# 1-Schematic_WaterTank_reciever_v1.net
KiCad netlist of a schematic drawn in EasyEDA
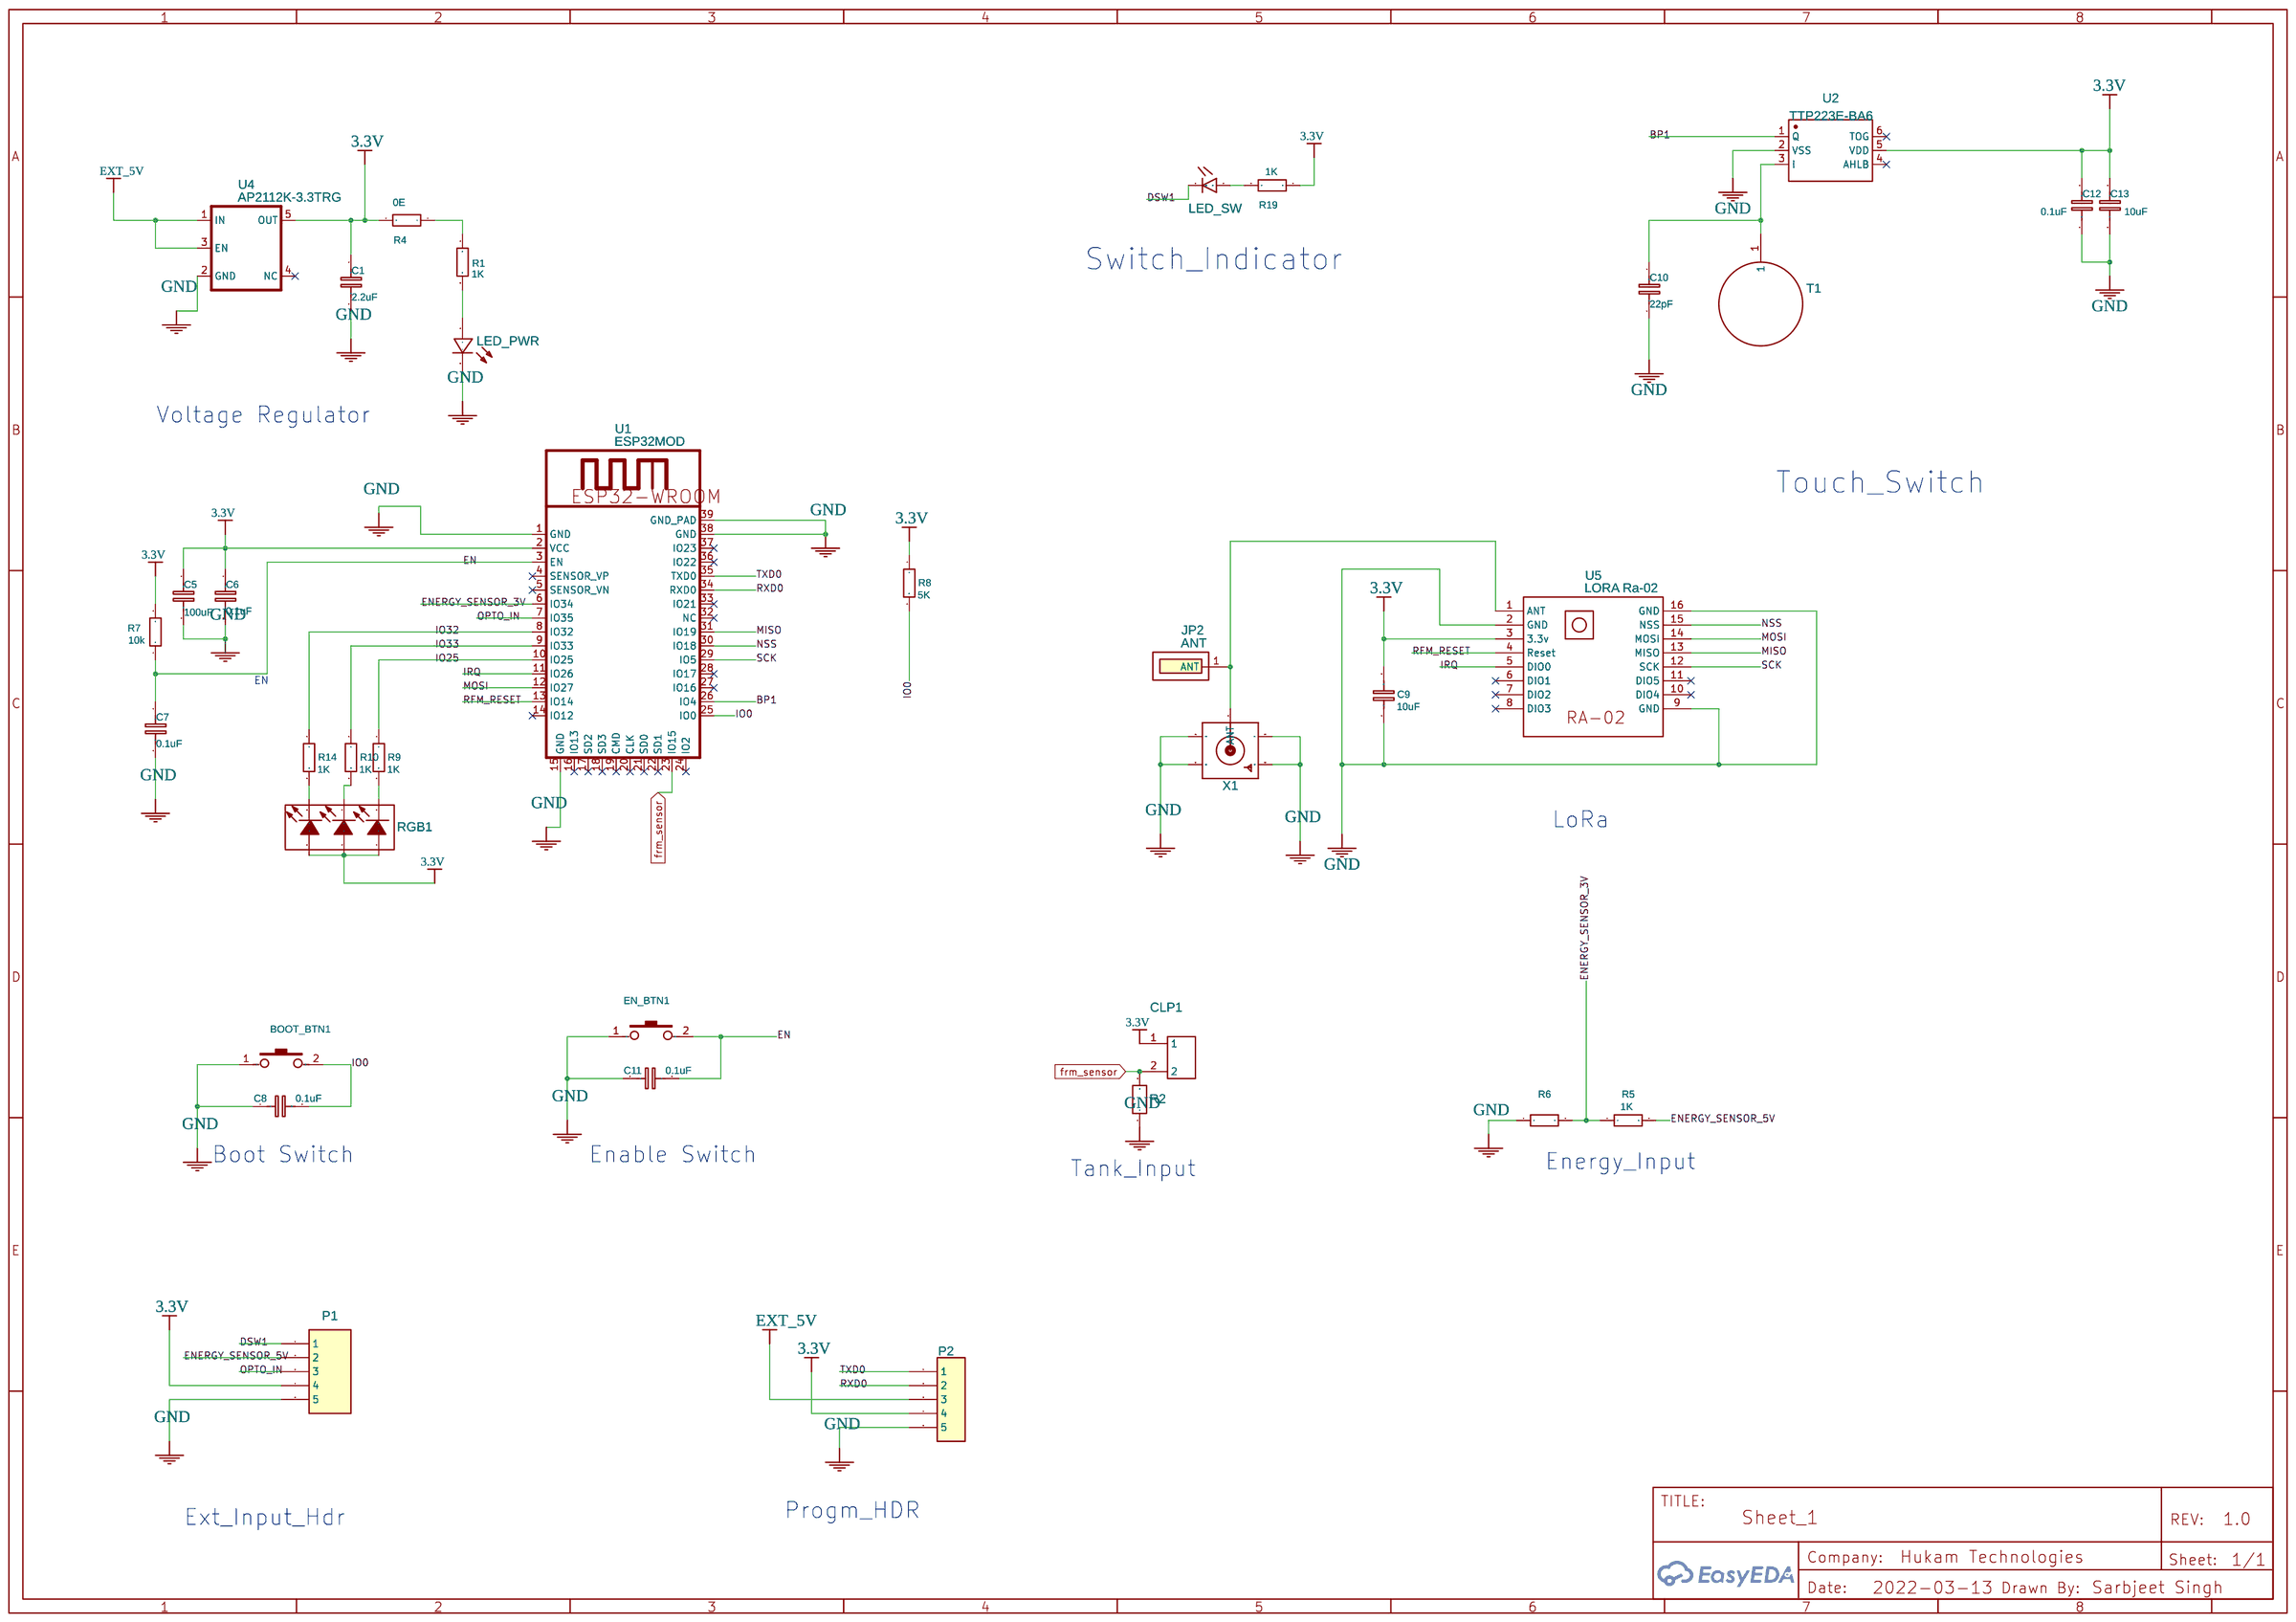
[diagram p0: schematic sheet]

(export (version "E")
  (design (tool "Eeschema 10.0.6"))
  (components
    (comp (ref "BOOT_BTN1")
      (value "SW1")
      (fields
        (field (name "BOM_Manufacturer Part") "Switch3x4x2")
        (field (name "BOM_Supplier Part") "C26638")
      )
      (libsource (lib "") (part "Unknown_195_-50"))
    )
    (comp (ref "C1")
      (value "2.2uF")
      (fields (field (name "BOM_Manufacturer Part") "?"))
      (libsource (lib "") (part "Capacitor_3"))
    )
    (comp (ref "C5")
      (value "100uF")
      (fields (field (name "BOM_Manufacturer Part") "?"))
      (libsource (lib "") (part "Capacitor_4"))
    )
    (comp (ref "C6")
      (value "0.1uF")
      (fields (field (name "BOM_Manufacturer Part") "?"))
      (libsource (lib "") (part "Capacitor_5"))
    )
    (comp (ref "C7")
      (value "0.1uF")
      (fields (field (name "BOM_Manufacturer Part") "?"))
      (libsource (lib "") (part "Capacitor_4"))
    )
    (comp (ref "C8")
      (value "0.1uF")
      (fields (field (name "BOM_Manufacturer Part") "?"))
      (libsource (lib "") (part "Capacitor_2"))
    )
    (comp (ref "C9")
      (value "10uF")
      (fields (field (name "BOM_Manufacturer Part") "?"))
      (libsource (lib "") (part "Capacitor_1"))
    )
    (comp (ref "C10")
      (value "22pF")
      (fields (field (name "BOM_Manufacturer Part") "?"))
      (libsource (lib "") (part "Capacitor"))
    )
    (comp (ref "C11")
      (value "0.1uF")
      (fields (field (name "BOM_Manufacturer Part") "?"))
      (libsource (lib "") (part "Capacitor_2"))
    )
    (comp (ref "C12")
      (value "0.1uF")
      (fields (field (name "BOM_Manufacturer Part") "?"))
      (libsource (lib "") (part "Capacitor"))
    )
    (comp (ref "C13")
      (value "10uF")
      (fields (field (name "BOM_Manufacturer Part") "?"))
      (libsource (lib "") (part "Capacitor"))
    )
    (comp (ref "CLP1") (value "JST_Conn_Water_Level") (libsource (lib "") (part "PCB JST XH2.54mm")))
    (comp (ref "EN_BTN1")
      (value "SW2")
      (fields
        (field (name "BOM_Manufacturer Part") "Switch3x4x2")
        (field (name "BOM_Supplier Part") "C26638")
      )
      (libsource (lib "") (part "Unknown_460_-70"))
    )
    (comp (ref "JP2")
      (value "ANT")
      (fields (field (name "BOM_Manufacturer Part") "?"))
      (libsource (lib "") (part "Unknown_875_-335"))
    )
    (comp (ref "LED_PWR")
      (value "LED-Blue(0603)")
      (fields
        (field (name "BOM_Manufacturer Part") "19-217/BHC-ZL1M2RY/3T")
        (field (name "BOM_Supplier Part") "undefined")
      )
      (libsource (lib "") (part "Unknown_325_-565"))
    )
    (comp (ref "LED_SW")
      (value "LED_Indicator")
      (fields (field (name "BOM_Manufacturer Part") "?"))
      (libsource (lib "") (part "Unknown_855_-680"))
    )
    (comp (ref "P1") (value "Ext_HDR") (libsource (lib "") (part "Header 5")))
    (comp (ref "P2")
      (value "HDR1X5")
      (fields (field (name "BOM_Manufacturer Part") "?"))
      (libsource (lib "") (part "Unknown_685_180"))
    )
    (comp (ref "R1")
      (value "1K")
      (fields (field (name "BOM_Manufacturer Part") "?"))
      (libsource (lib "") (part "Resistor"))
    )
    (comp (ref "R2") (value "1k") (libsource (lib "") (part "R_0603_EU")))
    (comp (ref "R4")
      (value "0E")
      (fields (field (name "BOM_Manufacturer Part") "?"))
      (libsource (lib "") (part "Resistor_2"))
    )
    (comp (ref "R5")
      (value "1K")
      (fields (field (name "BOM_Manufacturer Part") "?"))
      (libsource (lib "") (part "Resistor_1"))
    )
    (comp (ref "R6")
      (value "1K")
      (fields (field (name "BOM_Manufacturer Part") "?"))
      (libsource (lib "") (part "Resistor_1"))
    )
    (comp (ref "R7")
      (value "10k")
      (fields (field (name "BOM_Manufacturer Part") "?"))
      (libsource (lib "") (part "Resistor_3"))
    )
    (comp (ref "R8")
      (value "5K")
      (fields (field (name "BOM_Manufacturer Part") "?"))
      (libsource (lib "") (part "Resistor"))
    )
    (comp (ref "R9")
      (value "1K")
      (fields (field (name "BOM_Manufacturer Part") "?"))
      (libsource (lib "") (part "Resistor"))
    )
    (comp (ref "R10")
      (value "1K")
      (fields (field (name "BOM_Manufacturer Part") "?"))
      (libsource (lib "") (part "Resistor"))
    )
    (comp (ref "R14")
      (value "1K")
      (fields (field (name "BOM_Manufacturer Part") "?"))
      (libsource (lib "") (part "Resistor"))
    )
    (comp (ref "R19")
      (value "1K")
      (fields (field (name "BOM_Manufacturer Part") "?"))
      (libsource (lib "") (part "Resistor_2"))
    )
    (comp (ref "RGB1")
      (value "5050QRC")
      (fields (field (name "BOM_Supplier Part") "C42899"))
      (libsource (lib "") (part "Unknown_235_-220"))
    )
    (comp (ref "T1")
      (value "CapTouch Pad")
      (fields (field (name "BOM_Manufacturer Part") "?"))
      (libsource (lib "") (part "Unknown_1255_-625"))
    )
    (comp (ref "U1")
      (value "ESP32MOD")
      (fields (field (name "BOM_Manufacturer Part") "?"))
      (libsource (lib "") (part "Unknown_445_-380"))
    )
    (comp (ref "U2")
      (value "TTP223E-BA6")
      (fields (field (name "BOM_Supplier Part") "C129457"))
      (libsource (lib "") (part "Unknown_1305_-725"))
    )
    (comp (ref "U4")
      (value "AP2112K-3.3TRG")
      (fields (field (name "BOM_Manufacturer Part") "?"))
      (libsource (lib "") (part "Unknown_165_-625"))
    )
    (comp (ref "U5")
      (value "LORA Ra-02")
      (fields (field (name "BOM_Supplier Part") "RA-02"))
      (libsource (lib "") (part "Unknown_1145_-305"))
    )
    (comp (ref "X1")
      (value "SMACONNECTOR_EDGE_UFL")
      (fields (field (name "BOM_Manufacturer Part") "?"))
      (libsource (lib "") (part "Unknown_875_-275"))
    )
  )
  (nets
    (net (code "1") (name "/BP1") (class "Default")
      (node (ref "U1") (pin "26") (pinfunction "IO4_26") (pintype "unspecified"))
      (node (ref "U2") (pin "1") (pinfunction "Q_1") (pintype "unspecified"))
    )
    (net (code "2") (name "/DSW1") (class "Default")
      (node (ref "LED_SW") (pin "2") (pinfunction "CATHODE_2") (pintype "unspecified"))
      (node (ref "P1") (pin "1") (pinfunction "1_1") (pintype "unspecified"))
    )
    (net (code "3") (name "/EN") (class "Default")
      (node (ref "C11") (pin "2") (pinfunction "2_2") (pintype "unspecified"))
      (node (ref "C7") (pin "1") (pinfunction "1_1") (pintype "unspecified"))
      (node (ref "EN_BTN1") (pin "2") (pinfunction "2_2") (pintype "input"))
      (node (ref "R7") (pin "1") (pinfunction "1_1") (pintype "unspecified"))
      (node (ref "U1") (pin "3") (pinfunction "EN_3") (pintype "unspecified"))
    )
    (net (code "4") (name "/ENERGY_SENSOR_3V") (class "Default")
      (node (ref "R5") (pin "1") (pinfunction "1_1") (pintype "unspecified"))
      (node (ref "R6") (pin "2") (pinfunction "2_2") (pintype "unspecified"))
      (node (ref "U1") (pin "6") (pinfunction "IO34_6") (pintype "unspecified"))
    )
    (net (code "5") (name "/ENERGY_SENSOR_5V") (class "Default")
      (node (ref "P1") (pin "2") (pinfunction "2_2") (pintype "unspecified"))
      (node (ref "R5") (pin "2") (pinfunction "2_2") (pintype "unspecified"))
    )
    (net (code "6") (name "/IO0") (class "Default")
      (node (ref "BOOT_BTN1") (pin "2") (pinfunction "2_2") (pintype "input"))
      (node (ref "C8") (pin "2") (pinfunction "2_2") (pintype "unspecified"))
      (node (ref "R8") (pin "2") (pinfunction "2_2") (pintype "unspecified"))
      (node (ref "U1") (pin "25") (pinfunction "IO0_25") (pintype "unspecified"))
    )
    (net (code "7") (name "/IO25") (class "Default")
      (node (ref "R9") (pin "1") (pinfunction "1_1") (pintype "unspecified"))
      (node (ref "U1") (pin "10") (pinfunction "IO25_10") (pintype "unspecified"))
    )
    (net (code "8") (name "/IO32") (class "Default")
      (node (ref "R14") (pin "1") (pinfunction "1_1") (pintype "unspecified"))
      (node (ref "U1") (pin "8") (pinfunction "IO32_8") (pintype "unspecified"))
    )
    (net (code "9") (name "/IO33") (class "Default")
      (node (ref "R10") (pin "1") (pinfunction "1_1") (pintype "unspecified"))
      (node (ref "U1") (pin "9") (pinfunction "IO33_9") (pintype "unspecified"))
    )
    (net (code "10") (name "/IRQ") (class "Default")
      (node (ref "U1") (pin "11") (pinfunction "IO26_11") (pintype "unspecified"))
      (node (ref "U5") (pin "5") (pinfunction "DIO0_5") (pintype "unspecified"))
    )
    (net (code "11") (name "/MISO") (class "Default")
      (node (ref "U1") (pin "31") (pinfunction "IO19_31") (pintype "unspecified"))
      (node (ref "U5") (pin "13") (pinfunction "MISO_13") (pintype "unspecified"))
    )
    (net (code "12") (name "/MOSI") (class "Default")
      (node (ref "U1") (pin "12") (pinfunction "IO27_12") (pintype "unspecified"))
      (node (ref "U5") (pin "14") (pinfunction "MOSI_14") (pintype "unspecified"))
    )
    (net (code "13") (name "/NSS") (class "Default")
      (node (ref "U1") (pin "30") (pinfunction "IO18_30") (pintype "unspecified"))
      (node (ref "U5") (pin "15") (pinfunction "NSS_15") (pintype "unspecified"))
    )
    (net (code "14") (name "/OPTO_IN") (class "Default")
      (node (ref "P1") (pin "3") (pinfunction "3_3") (pintype "unspecified"))
      (node (ref "U1") (pin "7") (pinfunction "IO35_7") (pintype "unspecified"))
    )
    (net (code "15") (name "/RFM_RESET") (class "Default")
      (node (ref "U1") (pin "13") (pinfunction "IO14_13") (pintype "unspecified"))
      (node (ref "U5") (pin "4") (pinfunction "Reset_4") (pintype "unspecified"))
    )
    (net (code "16") (name "/RXD0") (class "Default")
      (node (ref "P2") (pin "2") (pinfunction "2_2") (pintype "unspecified"))
      (node (ref "U1") (pin "34") (pinfunction "RXD0_34") (pintype "unspecified"))
    )
    (net (code "17") (name "/SCK") (class "Default")
      (node (ref "U1") (pin "29") (pinfunction "IO5_29") (pintype "unspecified"))
      (node (ref "U5") (pin "12") (pinfunction "SCK_12") (pintype "unspecified"))
    )
    (net (code "18") (name "/TXD0") (class "Default")
      (node (ref "P2") (pin "1") (pinfunction "1_1") (pintype "unspecified"))
      (node (ref "U1") (pin "35") (pinfunction "TXD0_35") (pintype "unspecified"))
    )
    (net (code "19") (name "3.3V") (class "Default")
      (node (ref "C1") (pin "1") (pinfunction "1_1") (pintype "unspecified"))
      (node (ref "C12") (pin "1") (pinfunction "1_1") (pintype "unspecified"))
      (node (ref "C13") (pin "1") (pinfunction "1_1") (pintype "unspecified"))
      (node (ref "C5") (pin "1") (pinfunction "1_1") (pintype "unspecified"))
      (node (ref "C6") (pin "1") (pinfunction "1_1") (pintype "unspecified"))
      (node (ref "C9") (pin "2") (pinfunction "2_2") (pintype "unspecified"))
      (node (ref "CLP1") (pin "1") (pinfunction "1_1") (pintype "unspecified"))
      (node (ref "P1") (pin "4") (pinfunction "4_4") (pintype "unspecified"))
      (node (ref "P2") (pin "4") (pinfunction "4_4") (pintype "unspecified"))
      (node (ref "R19") (pin "1") (pinfunction "1_1") (pintype "unspecified"))
      (node (ref "R4") (pin "2") (pinfunction "2_2") (pintype "unspecified"))
      (node (ref "R7") (pin "2") (pinfunction "2_2") (pintype "unspecified"))
      (node (ref "R8") (pin "1") (pinfunction "1_1") (pintype "unspecified"))
      (node (ref "RGB1") (pin "1") (pinfunction "A_1") (pintype "unspecified"))
      (node (ref "RGB1") (pin "3") (pinfunction "A_3") (pintype "unspecified"))
      (node (ref "RGB1") (pin "5") (pinfunction "A_5") (pintype "unspecified"))
      (node (ref "U1") (pin "2") (pinfunction "VCC_2") (pintype "passive"))
      (node (ref "U2") (pin "5") (pinfunction "VDD_5") (pintype "unspecified"))
      (node (ref "U4") (pin "5") (pinfunction "OUT_5") (pintype "unspecified"))
      (node (ref "U5") (pin "3") (pinfunction "3.3v_3") (pintype "unspecified"))
    )
    (net (code "20") (name "EXT_5V") (class "Default")
      (node (ref "P2") (pin "3") (pinfunction "3_3") (pintype "unspecified"))
      (node (ref "U4") (pin "1") (pinfunction "IN_1") (pintype "input"))
      (node (ref "U4") (pin "3") (pinfunction "EN_3") (pintype "input"))
    )
    (net (code "21") (name "GND") (class "Default")
      (node (ref "BOOT_BTN1") (pin "1") (pinfunction "1_1") (pintype "input"))
      (node (ref "C1") (pin "2") (pinfunction "2_2") (pintype "unspecified"))
      (node (ref "C10") (pin "2") (pinfunction "2_2") (pintype "unspecified"))
      (node (ref "C11") (pin "1") (pinfunction "1_1") (pintype "unspecified"))
      (node (ref "C12") (pin "2") (pinfunction "2_2") (pintype "unspecified"))
      (node (ref "C13") (pin "2") (pinfunction "2_2") (pintype "unspecified"))
      (node (ref "C5") (pin "2") (pinfunction "2_2") (pintype "unspecified"))
      (node (ref "C6") (pin "2") (pinfunction "2_2") (pintype "unspecified"))
      (node (ref "C7") (pin "2") (pinfunction "2_2") (pintype "unspecified"))
      (node (ref "C8") (pin "1") (pinfunction "1_1") (pintype "unspecified"))
      (node (ref "C9") (pin "1") (pinfunction "1_1") (pintype "unspecified"))
      (node (ref "EN_BTN1") (pin "1") (pinfunction "1_1") (pintype "input"))
      (node (ref "LED_PWR") (pin "2") (pinfunction "-_2") (pintype "unspecified"))
      (node (ref "P1") (pin "5") (pinfunction "5_5") (pintype "unspecified"))
      (node (ref "P2") (pin "5") (pinfunction "5_5") (pintype "unspecified"))
      (node (ref "R2") (pin "1") (pinfunction "1_1") (pintype "unspecified"))
      (node (ref "R6") (pin "1") (pinfunction "1_1") (pintype "unspecified"))
      (node (ref "U1") (pin "1") (pinfunction "GND_1") (pintype "passive"))
      (node (ref "U1") (pin "15") (pinfunction "GND_15") (pintype "passive"))
      (node (ref "U1") (pin "38") (pinfunction "GND_38") (pintype "passive"))
      (node (ref "U1") (pin "39") (pinfunction "GND_PAD_39") (pintype "unspecified"))
      (node (ref "U2") (pin "2") (pinfunction "VSS_2") (pintype "unspecified"))
      (node (ref "U4") (pin "2") (pinfunction "GND_2") (pintype "input"))
      (node (ref "U5") (pin "16") (pinfunction "GND_16") (pintype "unspecified"))
      (node (ref "U5") (pin "2") (pinfunction "GND_2") (pintype "unspecified"))
      (node (ref "U5") (pin "9") (pinfunction "GND_9") (pintype "unspecified"))
      (node (ref "X1") (pin "GND@1") (pinfunction "GND1_GND@1") (pintype "passive"))
      (node (ref "X1") (pin "GND@2") (pinfunction "GND2_GND@2") (pintype "passive"))
      (node (ref "X1") (pin "GND@3") (pinfunction "GND3_GND@3") (pintype "passive"))
      (node (ref "X1") (pin "GND@4") (pinfunction "GND4_GND@4") (pintype "passive"))
    )
    (net (code "22") (name "Net-(JP2-ANT)") (class "Default")
      (node (ref "JP2") (pin "1") (pinfunction "ANT_1") (pintype "unspecified"))
      (node (ref "U5") (pin "1") (pinfunction "ANT_1") (pintype "unspecified"))
      (node (ref "X1") (pin "P") (pinfunction "ANT_P") (pintype "unspecified"))
    )
    (net (code "23") (name "Net-(LED_PWR-+)") (class "Default")
      (node (ref "LED_PWR") (pin "1") (pinfunction "+_1") (pintype "unspecified"))
      (node (ref "R1") (pin "2") (pinfunction "2_2") (pintype "unspecified"))
    )
    (net (code "24") (name "Net-(LED_SW-ANODE)") (class "Default")
      (node (ref "LED_SW") (pin "1") (pinfunction "ANODE_1") (pintype "unspecified"))
      (node (ref "R19") (pin "2") (pinfunction "2_2") (pintype "unspecified"))
    )
    (net (code "25") (name "Net-(R1-Pad1)") (class "Default")
      (node (ref "R1") (pin "1") (pinfunction "1_1") (pintype "unspecified"))
      (node (ref "R4") (pin "1") (pinfunction "1_1") (pintype "unspecified"))
    )
    (net (code "26") (name "Net-(R9-Pad2)") (class "Default")
      (node (ref "R9") (pin "2") (pinfunction "2_2") (pintype "unspecified"))
      (node (ref "RGB1") (pin "2") (pinfunction "K_2") (pintype "unspecified"))
    )
    (net (code "27") (name "Net-(R10-Pad2)") (class "Default")
      (node (ref "R10") (pin "2") (pinfunction "2_2") (pintype "unspecified"))
      (node (ref "RGB1") (pin "4") (pinfunction "K_4") (pintype "unspecified"))
    )
    (net (code "28") (name "Net-(R14-Pad2)") (class "Default")
      (node (ref "R14") (pin "2") (pinfunction "2_2") (pintype "unspecified"))
      (node (ref "RGB1") (pin "6") (pinfunction "K_6") (pintype "unspecified"))
    )
    (net (code "29") (name "Net-(U2-I)") (class "Default")
      (node (ref "C10") (pin "1") (pinfunction "1_1") (pintype "unspecified"))
      (node (ref "T1") (pin "1") (pinfunction "1_1") (pintype "unspecified"))
      (node (ref "U2") (pin "3") (pinfunction "I_3") (pintype "unspecified"))
    )
    (net (code "30") (name "frm_sensor") (class "Default")
      (node (ref "CLP1") (pin "2") (pinfunction "2_2") (pintype "unspecified"))
      (node (ref "R2") (pin "2") (pinfunction "2_2") (pintype "unspecified"))
      (node (ref "U1") (pin "23") (pinfunction "IO15_23") (pintype "unspecified"))
    )
    (net (code "31") (name "unconnected-(U1-CLK-Pad20)") (class "Default")
      (node (ref "U1") (pin "20") (pinfunction "CLK_20") (pintype "unspecified+no_connect"))
    )
    (net (code "32") (name "unconnected-(U1-CMD-Pad19)") (class "Default")
      (node (ref "U1") (pin "19") (pinfunction "CMD_19") (pintype "unspecified+no_connect"))
    )
    (net (code "33") (name "unconnected-(U1-IO2-Pad24)") (class "Default")
      (node (ref "U1") (pin "24") (pinfunction "IO2_24") (pintype "unspecified+no_connect"))
    )
    (net (code "34") (name "unconnected-(U1-IO12-Pad14)") (class "Default")
      (node (ref "U1") (pin "14") (pinfunction "IO12_14") (pintype "unspecified+no_connect"))
    )
    (net (code "35") (name "unconnected-(U1-IO13-Pad16)") (class "Default")
      (node (ref "U1") (pin "16") (pinfunction "IO13_16") (pintype "unspecified+no_connect"))
    )
    (net (code "36") (name "unconnected-(U1-IO16-Pad27)") (class "Default")
      (node (ref "U1") (pin "27") (pinfunction "IO16_27") (pintype "unspecified+no_connect"))
    )
    (net (code "37") (name "unconnected-(U1-IO17-Pad28)") (class "Default")
      (node (ref "U1") (pin "28") (pinfunction "IO17_28") (pintype "unspecified+no_connect"))
    )
    (net (code "38") (name "unconnected-(U1-IO21-Pad33)") (class "Default")
      (node (ref "U1") (pin "33") (pinfunction "IO21_33") (pintype "unspecified+no_connect"))
    )
    (net (code "39") (name "unconnected-(U1-IO22-Pad36)") (class "Default")
      (node (ref "U1") (pin "36") (pinfunction "IO22_36") (pintype "unspecified+no_connect"))
    )
    (net (code "40") (name "unconnected-(U1-IO23-Pad37)") (class "Default")
      (node (ref "U1") (pin "37") (pinfunction "IO23_37") (pintype "unspecified+no_connect"))
    )
    (net (code "41") (name "unconnected-(U1-NC-Pad32)") (class "Default")
      (node (ref "U1") (pin "32") (pinfunction "NC_32") (pintype "unspecified+no_connect"))
    )
    (net (code "42") (name "unconnected-(U1-SD0-Pad21)") (class "Default")
      (node (ref "U1") (pin "21") (pinfunction "SD0_21") (pintype "unspecified+no_connect"))
    )
    (net (code "43") (name "unconnected-(U1-SD1-Pad22)") (class "Default")
      (node (ref "U1") (pin "22") (pinfunction "SD1_22") (pintype "unspecified+no_connect"))
    )
    (net (code "44") (name "unconnected-(U1-SD2-Pad17)") (class "Default")
      (node (ref "U1") (pin "17") (pinfunction "SD2_17") (pintype "unspecified+no_connect"))
    )
    (net (code "45") (name "unconnected-(U1-SD3-Pad18)") (class "Default")
      (node (ref "U1") (pin "18") (pinfunction "SD3_18") (pintype "unspecified+no_connect"))
    )
    (net (code "46") (name "unconnected-(U1-SENSOR_VN-Pad5)") (class "Default")
      (node (ref "U1") (pin "5") (pinfunction "SENSOR_VN_5") (pintype "unspecified+no_connect"))
    )
    (net (code "47") (name "unconnected-(U1-SENSOR_VP-Pad4)") (class "Default")
      (node (ref "U1") (pin "4") (pinfunction "SENSOR_VP_4") (pintype "unspecified+no_connect"))
    )
    (net (code "48") (name "unconnected-(U2-AHLB-Pad4)") (class "Default")
      (node (ref "U2") (pin "4") (pinfunction "AHLB_4") (pintype "unspecified+no_connect"))
    )
    (net (code "49") (name "unconnected-(U2-TOG-Pad6)") (class "Default")
      (node (ref "U2") (pin "6") (pinfunction "TOG_6") (pintype "unspecified+no_connect"))
    )
    (net (code "50") (name "unconnected-(U4-NC-Pad4)") (class "Default")
      (node (ref "U4") (pin "4") (pinfunction "NC_4") (pintype "input+no_connect"))
    )
    (net (code "51") (name "unconnected-(U5-DIO1-Pad6)") (class "Default")
      (node (ref "U5") (pin "6") (pinfunction "DIO1_6") (pintype "unspecified+no_connect"))
    )
    (net (code "52") (name "unconnected-(U5-DIO2-Pad7)") (class "Default")
      (node (ref "U5") (pin "7") (pinfunction "DIO2_7") (pintype "unspecified+no_connect"))
    )
    (net (code "53") (name "unconnected-(U5-DIO3-Pad8)") (class "Default")
      (node (ref "U5") (pin "8") (pinfunction "DIO3_8") (pintype "unspecified+no_connect"))
    )
    (net (code "54") (name "unconnected-(U5-DIO4-Pad10)") (class "Default")
      (node (ref "U5") (pin "10") (pinfunction "DIO4_10") (pintype "unspecified+no_connect"))
    )
    (net (code "55") (name "unconnected-(U5-DIO5-Pad11)") (class "Default")
      (node (ref "U5") (pin "11") (pinfunction "DIO5_11") (pintype "unspecified+no_connect"))
    )
  )
)
